# JacdacAccelerometer_30.net
KiCad netlist of a schematic drawn in Altium Designer
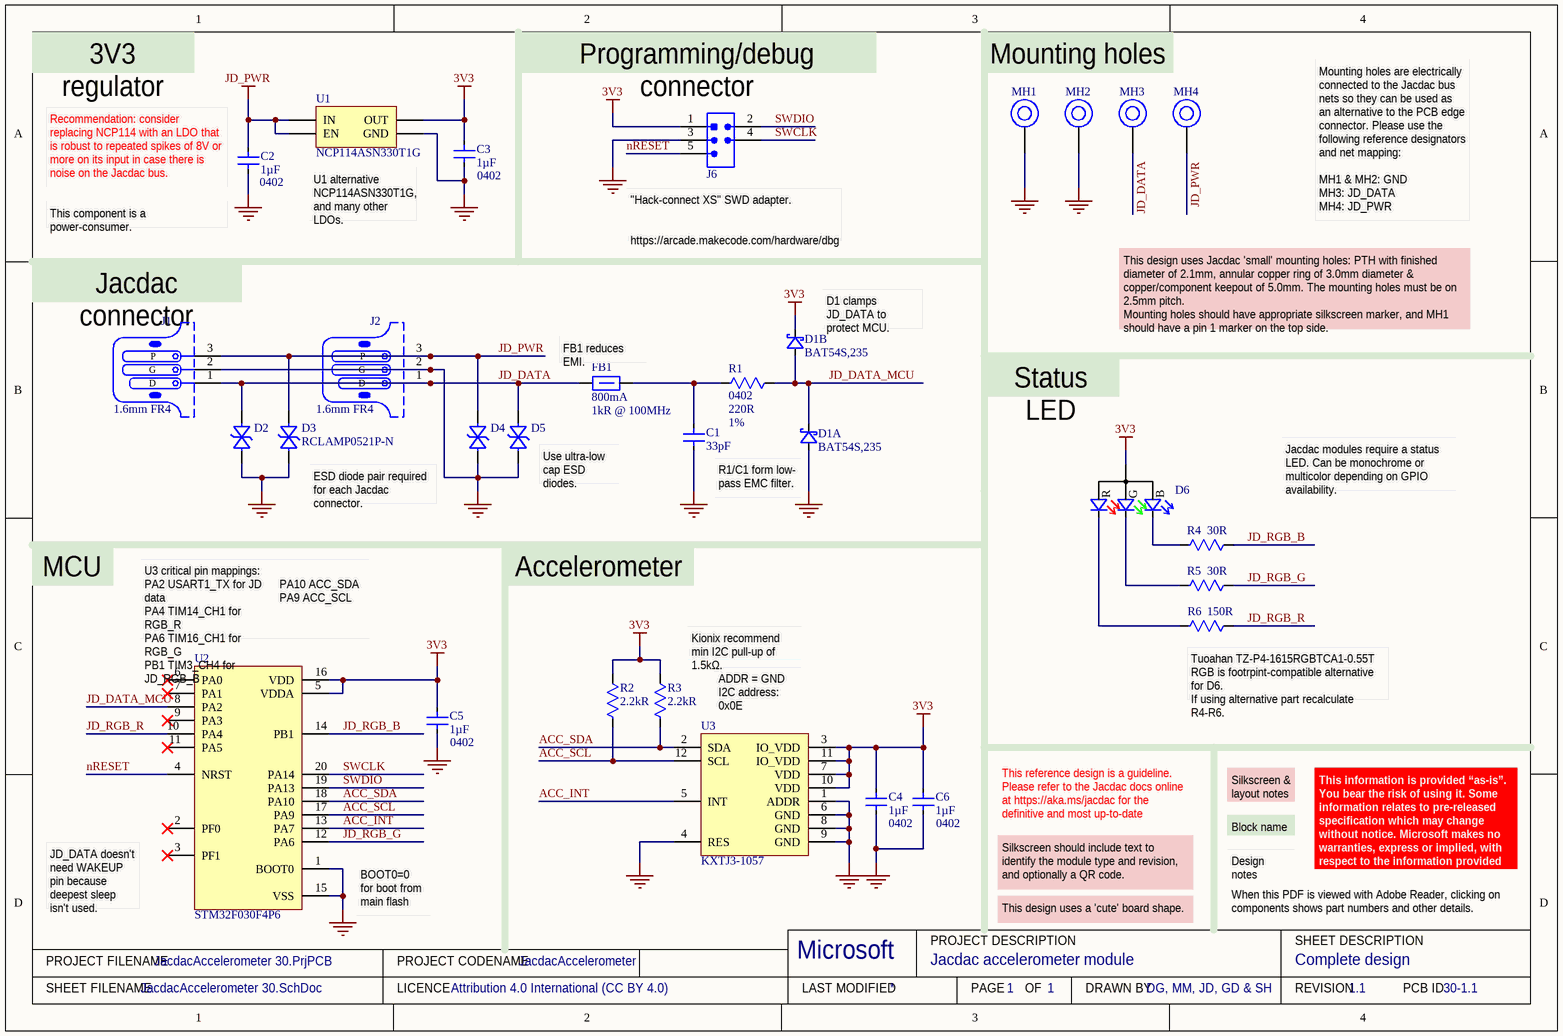
[diagram p0: JacdacAccelerometer 30.SchDoc]

(export (version "E")
  (design (tool "Eeschema 10.0.6"))
  (components
    (comp (ref "C1")
      (value "CL05C330JB51PNC")
      (footprint "C0402_0.55MM - without outline")
      (description "CAP CER 33PF 50V NP0 0402")
      (fields
        (field (name "MANUFACTURER") "Samsung")
        (field (name "TOLERANCE") "5%")
        (field (name "CAPACITANCE") "33pF")
        (field (name "CHECKED") "?")
        (field (name "CREATED") "DG")
      )
      (libsource (lib "Samsung") (part "CL05C330JB51PNC"))
    )
    (comp (ref "C2")
      (value "CL05A105KP5NNNC")
      (footprint "C0402_0.55MM - without outline")
      (description "CAP CER 1UF 10V X5R 0402")
      (fields
        (field (name "MANUFACTURER") "Samsung")
        (field (name "TOLERANCE") "10%")
        (field (name "CAPACITANCE") "1µF")
        (field (name "CASE CODE (IMPERIAL)") "0402")
        (field (name "CREATED") "DG")
        (field (name "CHECKED") "?")
      )
      (libsource (lib "Samsung") (part "CL05A105KP5NNNC"))
    )
    (comp (ref "C3")
      (value "CL05A105KP5NNNC")
      (footprint "C0402_0.55MM - without outline")
      (description "CAP CER 1UF 10V X5R 0402")
      (fields
        (field (name "MANUFACTURER") "Samsung")
        (field (name "TOLERANCE") "10%")
        (field (name "CAPACITANCE") "1µF")
        (field (name "CASE CODE (IMPERIAL)") "0402")
        (field (name "CREATED") "DG")
        (field (name "CHECKED") "?")
      )
      (libsource (lib "Samsung") (part "CL05A105KP5NNNC"))
    )
    (comp (ref "C4")
      (value "CL05A105KP5NNNC")
      (footprint "C0402_0.55MM - without outline")
      (description "CAP CER 1UF 10V X5R 0402")
      (fields
        (field (name "MANUFACTURER") "Samsung")
        (field (name "TOLERANCE") "10%")
        (field (name "CAPACITANCE") "1µF")
        (field (name "CASE CODE (IMPERIAL)") "0402")
        (field (name "CREATED") "DG")
        (field (name "CHECKED") "?")
      )
      (libsource (lib "Samsung") (part "CL05A105KP5NNNC"))
    )
    (comp (ref "C5")
      (value "CL05A105KP5NNNC")
      (footprint "C0402_0.55MM - without outline")
      (description "CAP CER 1UF 10V X5R 0402")
      (fields
        (field (name "MANUFACTURER") "Samsung")
        (field (name "TOLERANCE") "10%")
        (field (name "CAPACITANCE") "1µF")
        (field (name "CASE CODE (IMPERIAL)") "0402")
        (field (name "CREATED") "DG")
        (field (name "CHECKED") "?")
      )
      (libsource (lib "Samsung") (part "CL05A105KP5NNNC"))
    )
    (comp (ref "C6")
      (value "CL05A105KP5NNNC")
      (footprint "C0402_0.55MM - without outline")
      (description "CAP CER 1UF 10V X5R 0402")
      (fields
        (field (name "MANUFACTURER") "Samsung")
        (field (name "TOLERANCE") "10%")
        (field (name "CAPACITANCE") "1µF")
        (field (name "CASE CODE (IMPERIAL)") "0402")
        (field (name "CREATED") "DG")
        (field (name "CHECKED") "?")
      )
      (libsource (lib "Samsung") (part "CL05A105KP5NNNC"))
    )
    (comp (ref "D1")
      (value "BAT54S")
      (footprint "NXP-BAT54S-TO-236AB - without outline")
      (description "DIODE ARRAY SCHOTTKY 30V SOT23")
      (fields (field (name "MANUFACTURER") "Nexperia") (field (name "MANUFACTURER PART NUMBER") "BAT54S,235"))
      (libsource (lib "NXP") (part "BAT54S"))
    )
    (comp (ref "D2")
      (value "RCLAMP0521P-N")
      (footprint "TVS 0402 - L")
      (description "Bidirectional 5V (Max) 6V 16V 3.5A (8/20us) 0402 TVS RoHS")
      (fields
        (field (name "MANUFACTURER") "Born Semiconductor")
        (field (name "CREATED BY") "D Gakure")
        (field (name "CHECKED BY") "?")
      )
      (libsource (lib "BornSemiconductor") (part "RCLAMP0521P-N"))
    )
    (comp (ref "D3")
      (value "RCLAMP0521P-N")
      (footprint "TVS 0402 - L")
      (description "Bidirectional 5V (Max) 6V 16V 3.5A (8/20us) 0402 TVS RoHS")
      (fields
        (field (name "MANUFACTURER") "Born Semiconductor")
        (field (name "MANUFACTURER PART NUMBER") "RCLAMP0521P-N")
        (field (name "CREATED BY") "D Gakure")
        (field (name "CHECKED BY") "?")
      )
      (libsource (lib "BornSemiconductor") (part "RCLAMP0521P-N"))
    )
    (comp (ref "D4")
      (value "RCLAMP0521P-N")
      (footprint "TVS 0402 - L")
      (description "Bidirectional 5V (Max) 6V 16V 3.5A (8/20us) 0402 TVS RoHS")
      (fields
        (field (name "MANUFACTURER") "Born Semiconductor")
        (field (name "CREATED BY") "D Gakure")
        (field (name "CHECKED BY") "?")
      )
      (libsource (lib "BornSemiconductor") (part "RCLAMP0521P-N"))
    )
    (comp (ref "D5")
      (value "RCLAMP0521P-N")
      (footprint "TVS 0402 - L")
      (description "Bidirectional 5V (Max) 6V 16V 3.5A (8/20us) 0402 TVS RoHS")
      (fields
        (field (name "MANUFACTURER") "Born Semiconductor")
        (field (name "CREATED BY") "D Gakure")
        (field (name "CHECKED BY") "?")
      )
      (libsource (lib "BornSemiconductor") (part "RCLAMP0521P-N"))
    )
    (comp (ref "D6")
      (value "HSMF-C114")
      (footprint "HSMF-C114")
      (fields
        (field (name "MANUFACTURER") "Broadcom Avago")
        (field (name "CREATED BY") "D. Gakure")
        (field (name "CHECKED BY") "?")
      )
      (libsource (lib "BroadcomLimited") (part "HSMF-C114"))
    )
    (comp (ref "FB1")
      (value "TDK MPZ1608S102ATA00")
      (footprint "TDK MPZ1608 0.8mm - without outline")
      (description "0603 1k@100MHz 0.8A chip")
      (fields
        (field (name "TOLERANCE") "25%")
        (field (name "MANUFACTURER") "TDK")
        (field (name "CURRENT RATING") "800mA")
        (field (name "IMPEDANCE") "1kR @ 100MHz")
      )
      (libsource (lib "TDK") (part "TDK MPZ1608S102ATA00"))
    )
    (comp (ref "J1")
      (value "3 pin JACDAC edge connector")
      (footprint "JACDAC_EDGE_CONNECTOR_NO_TRACES")
      (description "3 pin Jacdac edge connector 1.27mm pitch")
      (fields
        (field (name "MANUFACTURER PART NUMBER") "JACDAC_EDGE_CONNECTOR")
        (field (name "PCB TYPE") "1.6mm FR4")
        (field (name "CHECKED BY") "?")
        (field (name "CREATED BY") "D. Gakure")
      )
      (libsource (lib "generic-con") (part "Jacdac edge connector"))
    )
    (comp (ref "J2")
      (value "3 pin JACDAC edge connector")
      (footprint "JACDAC_EDGE_CONNECTOR_NO_TRACES")
      (description "3 pin Jacdac edge connector 1.27mm pitch")
      (fields
        (field (name "MANUFACTURER PART NUMBER") "JACDAC_EDGE_CONNECTOR")
        (field (name "PCB TYPE") "1.6mm FR4")
        (field (name "CHECKED BY") "?")
        (field (name "CREATED BY") "D. Gakure")
      )
      (libsource (lib "generic-con") (part "Jacdac edge connector"))
    )
    (comp (ref "J6")
      (value "Hack Connect Mini 1.27 mm pitch 2-row")
      (footprint "HACK_CONNECT_MINI_5_X_1_27")
      (libsource (lib "HackConnect") (part "HACK_CONNECT_MINI"))
    )
    (comp (ref "MH1")
      (value "MH_5.0MMK_3.0MMC_2.1MMD_PTH")
      (footprint "MH_5.0MMK_3.0MMC_2.1MMD_PTH:MH_5.0MMK_3.0MMC_2.1MMD_PTH")
      (description "Mounting Hole 5.0mm keepout, 3.0mm annualar ring and 2.1mm Drill PTH")
      (libsource (lib "generic") (part "MH_5.0MMK_3.0MMC_2.1MMD_PTH"))
    )
    (comp (ref "MH2")
      (value "MH_5.0MMK_3.0MMC_2.1MMD_PTH")
      (footprint "MH_5.0MMK_3.0MMC_2.1MMD_PTH:MH_5.0MMK_3.0MMC_2.1MMD_PTH")
      (description "Mounting Hole 5.0mm keepout, 3.0mm annualar ring and 2.1mm Drill PTH")
      (libsource (lib "generic") (part "MH_5.0MMK_3.0MMC_2.1MMD_PTH"))
    )
    (comp (ref "MH3")
      (value "MH_5.0MMK_3.0MMC_2.1MMD_PTH")
      (footprint "MH_5.0MMK_3.0MMC_2.1MMD_PTH:MH_5.0MMK_3.0MMC_2.1MMD_PTH")
      (description "Mounting Hole 5.0mm keepout, 3.0mm annualar ring and 2.1mm Drill PTH")
      (libsource (lib "generic") (part "MH_5.0MMK_3.0MMC_2.1MMD_PTH"))
    )
    (comp (ref "MH4")
      (value "MH_5.0MMK_3.0MMC_2.1MMD_PTH")
      (footprint "MH_5.0MMK_3.0MMC_2.1MMD_PTH")
      (description "Mounting Hole 5.0mm keepout, 3.0mm annualar ring and 2.1mm Drill PTH")
      (libsource (lib "generic") (part "MH_5.0MMK_3.0MMC_2.1MMD_PTH"))
    )
    (comp (ref "R1")
      (value "RC0402FR-07220RL")
      (footprint "R0402 - Without outline")
      (description "RES SMD 220 OHM 1% 1/16W 0402")
      (fields
        (field (name "MANUFACTURER") "Yageo")
        (field (name "CASE CODE (IMPERIAL)") "0402")
        (field (name "RESISTANCE") "220R")
        (field (name "TOLERANCE") "1%")
        (field (name "CREATED") "D.G")
        (field (name "CHECKED") "?")
      )
      (libsource (lib "Yageo") (part "RC0402FR-07220RL"))
    )
    (comp (ref "R2")
      (value "RC0402FR-072K2L")
      (footprint "R0402 - Without outline")
      (description "RES SMD 2.2K OHM 1% 1/16W 0402")
      (fields
        (field (name "MANUFACTURER") "Yageo")
        (field (name "TOLERANCE") "1%")
        (field (name "RESISTANCE") "2.2kR")
        (field (name "CREATED BY") "D. Gakure")
        (field (name "BY") "?")
      )
      (libsource (lib "Yageo") (part "RC0402FR-072K2L"))
    )
    (comp (ref "R3")
      (value "RC0402FR-072K2L")
      (footprint "R0402 - Without outline")
      (description "RES SMD 2.2K OHM 1% 1/16W 0402")
      (fields
        (field (name "MANUFACTURER") "Yageo")
        (field (name "TOLERANCE") "1%")
        (field (name "RESISTANCE") "2.2kR")
        (field (name "CREATED BY") "D. Gakure")
        (field (name "BY") "?")
      )
      (libsource (lib "Yageo") (part "RC0402FR-072K2L"))
    )
    (comp (ref "R4")
      (value "RC0402FR-0730RL")
      (footprint "R0402 - Without outline")
      (description "RES SMD 30 OHM 1% 1/16W 0402")
      (fields
        (field (name "MANUFACTURER") "Yageo")
        (field (name "RESISTANCE") "30R")
        (field (name "TOLERANCE") "1%")
        (field (name "CREATED BY") "D. Gakure")
        (field (name "CHECKED BY") "?")
      )
      (libsource (lib "Yageo") (part "RC0402FR-0730RL"))
    )
    (comp (ref "R5")
      (value "RC0402FR-0730RL")
      (footprint "R0402 - Without outline")
      (description "RES SMD 30 OHM 1% 1/16W 0402")
      (fields
        (field (name "MANUFACTURER") "Yageo")
        (field (name "RESISTANCE") "30R")
        (field (name "TOLERANCE") "1%")
        (field (name "CREATED BY") "D. Gakure")
        (field (name "CHECKED BY") "?")
      )
      (libsource (lib "Yageo") (part "RC0402FR-0730RL"))
    )
    (comp (ref "R6")
      (value "RC0402FR-07150RL")
      (footprint "R0402 - Without outline")
      (description "RES SMD 150 OHM 1% 1/16W 0402")
      (fields
        (field (name "MANUFACTURER") "Yageo")
        (field (name "RESISTANCE") "150R")
        (field (name "TOLERANCE") "1%")
        (field (name "CREATED BY") "D. Gakure")
        (field (name "CHECKED BY") "?")
      )
      (libsource (lib "Yageo") (part "RC0402FR-07150RL"))
    )
    (comp (ref "U1")
      (value "LDO 3.3V/300 mA")
      (footprint "ON_SEMI-SOT23-5 - without outline")
      (fields
        (field (name "MANUFACTURER") "ON Semiconductor")
        (field (name "MANUFACTURER PART NUMBER") "NCP114ASN330T1G")
        (field (name "CREATED") "DG")
        (field (name "CHECKED") "?")
      )
      (libsource (lib "OnSemiconductor") (part "NCP114ASN330T1G"))
    )
    (comp (ref "U2")
      (value "STM32F030F4P6")
      (footprint "20-TSSOP - without outline")
      (description "ARM Cortex-M0 STM32F0 Microcontroller IC 32-Bit 48MHz 16KB (16K x 8) FLASH")
      (fields
        (field (name "MANUFACTURER") "STMicroelectronics")
        (field (name "MANUFACTURER PART NUMBER") "STM32F030F4P6")
        (field (name "CREATED") "DG")
        (field (name "CHECKED") "?")
        (field (name "CREATED BY") "D. Gakure")
        (field (name "CHECKED BY") "?")
      )
      (libsource (lib "ST") (part "ST STM32F030F4P6"))
    )
    (comp (ref "U3")
      (value "KXTJ3-1057")
      (footprint "KXTJ3-1057")
      (description "KIONIX - KXTJ3-1057 - MEMS ACCELEROMETER, 2G/4G/8G, LGA-12")
      (fields
        (field (name "MANUFACTURER") "Rohm Kionix")
        (field (name "MANUFACTURER PART NUMBER") "KXTJ3-1057")
        (field (name "CREATED BY") "D Gakure")
        (field (name "CHECKED BY") "?")
      )
      (libsource (lib "KionixInc") (part "KXTJ3-1057"))
    )
  )
  (nets
    (net (code "1") (name "/ACC_INT") (class "Default")
      (node (ref "U2") (pin "13") (pinfunction "PA7_13") (pintype "passive"))
      (node (ref "U3") (pin "5") (pinfunction "INT_5") (pintype "passive"))
    )
    (net (code "2") (name "/ACC_SCL") (class "Default")
      (node (ref "R2") (pin "2") (pinfunction "2_2") (pintype "passive"))
      (node (ref "U2") (pin "17") (pinfunction "PA9_17") (pintype "passive"))
      (node (ref "U3") (pin "12") (pinfunction "SCL_12") (pintype "passive"))
    )
    (net (code "3") (name "/ACC_SDA") (class "Default")
      (node (ref "R3") (pin "2") (pinfunction "2_2") (pintype "passive"))
      (node (ref "U2") (pin "18") (pinfunction "PA10_18") (pintype "passive"))
      (node (ref "U3") (pin "2") (pinfunction "SDA_2") (pintype "passive"))
    )
    (net (code "4") (name "/JD_DATA") (class "Default")
      (node (ref "D2") (pin "1") (pinfunction "K_1") (pintype "passive"))
      (node (ref "D5") (pin "1") (pinfunction "K_1") (pintype "passive"))
      (node (ref "FB1") (pin "1") (pinfunction "1_1") (pintype "passive"))
      (node (ref "J1") (pin "1") (pinfunction "D_1") (pintype "passive"))
      (node (ref "J2") (pin "1") (pinfunction "D_1") (pintype "passive"))
      (node (ref "MH3") (pin "1") (pinfunction "1_1") (pintype "passive"))
    )
    (net (code "5") (name "/JD_DATA_MCU") (class "Default")
      (node (ref "D1") (pin "3") (pinfunction "K_3") (pintype "passive"))
      (node (ref "R1") (pin "1") (pinfunction "1_1") (pintype "passive"))
      (node (ref "U2") (pin "8") (pinfunction "PA2_8") (pintype "passive"))
    )
    (net (code "6") (name "/JD_RGB_B") (class "Default")
      (node (ref "R4") (pin "2") (pinfunction "2_2") (pintype "passive"))
      (node (ref "U2") (pin "14") (pinfunction "PB1_14") (pintype "passive"))
    )
    (net (code "7") (name "/JD_RGB_G") (class "Default")
      (node (ref "R5") (pin "2") (pinfunction "2_2") (pintype "passive"))
      (node (ref "U2") (pin "12") (pinfunction "PA6_12") (pintype "passive"))
    )
    (net (code "8") (name "/JD_RGB_R") (class "Default")
      (node (ref "R6") (pin "2") (pinfunction "2_2") (pintype "passive"))
      (node (ref "U2") (pin "10") (pinfunction "PA4_10") (pintype "passive"))
    )
    (net (code "9") (name "/SWCLK") (class "Default")
      (node (ref "J6") (pin "4") (pinfunction "SWCLK_4") (pintype "passive"))
      (node (ref "U2") (pin "20") (pinfunction "PA14_20") (pintype "passive"))
    )
    (net (code "10") (name "/SWDIO") (class "Default")
      (node (ref "J6") (pin "2") (pinfunction "SWDIO_2") (pintype "passive"))
      (node (ref "U2") (pin "19") (pinfunction "PA13_19") (pintype "passive"))
    )
    (net (code "11") (name "/nRESET") (class "Default")
      (node (ref "J6") (pin "5") (pinfunction "RESET_5") (pintype "passive"))
      (node (ref "U2") (pin "4") (pinfunction "NRST_4") (pintype "passive"))
    )
    (net (code "12") (name "3V3") (class "Default")
      (node (ref "C3") (pin "2") (pinfunction "2_2") (pintype "passive"))
      (node (ref "C4") (pin "2") (pinfunction "2_2") (pintype "passive"))
      (node (ref "C5") (pin "2") (pinfunction "2_2") (pintype "passive"))
      (node (ref "C6") (pin "2") (pinfunction "2_2") (pintype "passive"))
      (node (ref "D1") (pin "2") (pinfunction "K_2") (pintype "passive"))
      (node (ref "D6") (pin "1") (pinfunction "A_1") (pintype "passive"))
      (node (ref "J6") (pin "1") (pinfunction "VCC_1") (pintype "passive"))
      (node (ref "R2") (pin "1") (pinfunction "1_1") (pintype "passive"))
      (node (ref "R3") (pin "1") (pinfunction "1_1") (pintype "passive"))
      (node (ref "U1") (pin "5") (pinfunction "OUT_5") (pintype "passive"))
      (node (ref "U2") (pin "16") (pinfunction "VDD_16") (pintype "power_in"))
      (node (ref "U2") (pin "5") (pinfunction "VDDA_5") (pintype "power_in"))
      (node (ref "U3") (pin "10") (pinfunction "VDD_10") (pintype "power_in"))
      (node (ref "U3") (pin "11") (pinfunction "IO_VDD_11") (pintype "power_in"))
      (node (ref "U3") (pin "3") (pinfunction "IO_VDD_3") (pintype "power_in"))
      (node (ref "U3") (pin "7") (pinfunction "VDD_7") (pintype "power_in"))
    )
    (net (code "13") (name "GND") (class "Default")
      (node (ref "C1") (pin "1") (pinfunction "1_1") (pintype "passive"))
      (node (ref "C2") (pin "1") (pinfunction "1_1") (pintype "passive"))
      (node (ref "C3") (pin "1") (pinfunction "1_1") (pintype "passive"))
      (node (ref "C4") (pin "1") (pinfunction "1_1") (pintype "passive"))
      (node (ref "C5") (pin "1") (pinfunction "1_1") (pintype "passive"))
      (node (ref "C6") (pin "1") (pinfunction "1_1") (pintype "passive"))
      (node (ref "D1") (pin "1") (pinfunction "A_1") (pintype "passive"))
      (node (ref "D2") (pin "2") (pinfunction "A_2") (pintype "passive"))
      (node (ref "D3") (pin "2") (pinfunction "A_2") (pintype "passive"))
      (node (ref "D4") (pin "2") (pinfunction "A_2") (pintype "passive"))
      (node (ref "D5") (pin "2") (pinfunction "A_2") (pintype "passive"))
      (node (ref "J1") (pin "2") (pinfunction "G_2") (pintype "passive"))
      (node (ref "J2") (pin "2") (pinfunction "G_2") (pintype "passive"))
      (node (ref "J6") (pin "3") (pinfunction "GND_3") (pintype "passive"))
      (node (ref "MH1") (pin "1") (pinfunction "1_1") (pintype "passive"))
      (node (ref "MH2") (pin "1") (pinfunction "1_1") (pintype "passive"))
      (node (ref "U1") (pin "2") (pinfunction "GND_2") (pintype "passive"))
      (node (ref "U2") (pin "1") (pinfunction "BOOT0_1") (pintype "passive"))
      (node (ref "U2") (pin "15") (pinfunction "VSS_15") (pintype "power_in"))
      (node (ref "U3") (pin "1") (pinfunction "ADDR_1") (pintype "passive"))
      (node (ref "U3") (pin "4") (pinfunction "RES_4") (pintype "passive"))
      (node (ref "U3") (pin "6") (pinfunction "GND_6") (pintype "passive"))
      (node (ref "U3") (pin "8") (pinfunction "GND_8") (pintype "passive"))
      (node (ref "U3") (pin "9") (pinfunction "GND_9") (pintype "passive"))
    )
    (net (code "14") (name "JD_PWR") (class "Default")
      (node (ref "C2") (pin "2") (pinfunction "2_2") (pintype "passive"))
      (node (ref "D3") (pin "1") (pinfunction "K_1") (pintype "passive"))
      (node (ref "D4") (pin "1") (pinfunction "K_1") (pintype "passive"))
      (node (ref "J1") (pin "3") (pinfunction "P_3") (pintype "passive"))
      (node (ref "J2") (pin "3") (pinfunction "P_3") (pintype "passive"))
      (node (ref "MH4") (pin "1") (pinfunction "1_1") (pintype "passive"))
      (node (ref "U1") (pin "1") (pinfunction "IN_1") (pintype "passive"))
      (node (ref "U1") (pin "3") (pinfunction "EN_3") (pintype "passive"))
    )
    (net (code "15") (name "Net-(C1-Pad2)") (class "Default")
      (node (ref "C1") (pin "2") (pinfunction "2_2") (pintype "passive"))
      (node (ref "FB1") (pin "2") (pinfunction "2_2") (pintype "passive"))
      (node (ref "R1") (pin "2") (pinfunction "2_2") (pintype "passive"))
    )
    (net (code "16") (name "Net-(D6-B)") (class "Default")
      (node (ref "D6") (pin "4") (pinfunction "B_4") (pintype "passive"))
      (node (ref "R4") (pin "1") (pinfunction "1_1") (pintype "passive"))
    )
    (net (code "17") (name "Net-(D6-G)") (class "Default")
      (node (ref "D6") (pin "3") (pinfunction "G_3") (pintype "passive"))
      (node (ref "R5") (pin "1") (pinfunction "1_1") (pintype "passive"))
    )
    (net (code "18") (name "Net-(D6-R)") (class "Default")
      (node (ref "D6") (pin "2") (pinfunction "R_2") (pintype "passive"))
      (node (ref "R6") (pin "1") (pinfunction "1_1") (pintype "passive"))
    )
    (net (code "19") (name "unconnected-(U2-PA0-Pad6)") (class "Default")
      (node (ref "U2") (pin "6") (pinfunction "PA0_6") (pintype "passive+no_connect"))
    )
    (net (code "20") (name "unconnected-(U2-PA1-Pad7)") (class "Default")
      (node (ref "U2") (pin "7") (pinfunction "PA1_7") (pintype "passive+no_connect"))
    )
    (net (code "21") (name "unconnected-(U2-PA3-Pad9)") (class "Default")
      (node (ref "U2") (pin "9") (pinfunction "PA3_9") (pintype "passive+no_connect"))
    )
    (net (code "22") (name "unconnected-(U2-PA5-Pad11)") (class "Default")
      (node (ref "U2") (pin "11") (pinfunction "PA5_11") (pintype "passive+no_connect"))
    )
    (net (code "23") (name "unconnected-(U2-PF0-Pad2)") (class "Default")
      (node (ref "U2") (pin "2") (pinfunction "PF0_2") (pintype "passive+no_connect"))
    )
    (net (code "24") (name "unconnected-(U2-PF1-Pad3)") (class "Default")
      (node (ref "U2") (pin "3") (pinfunction "PF1_3") (pintype "passive+no_connect"))
    )
  )
)
